# 13_PHY_FE_33-40.net
KiCad netlist of a schematic drawn in Altium Designer
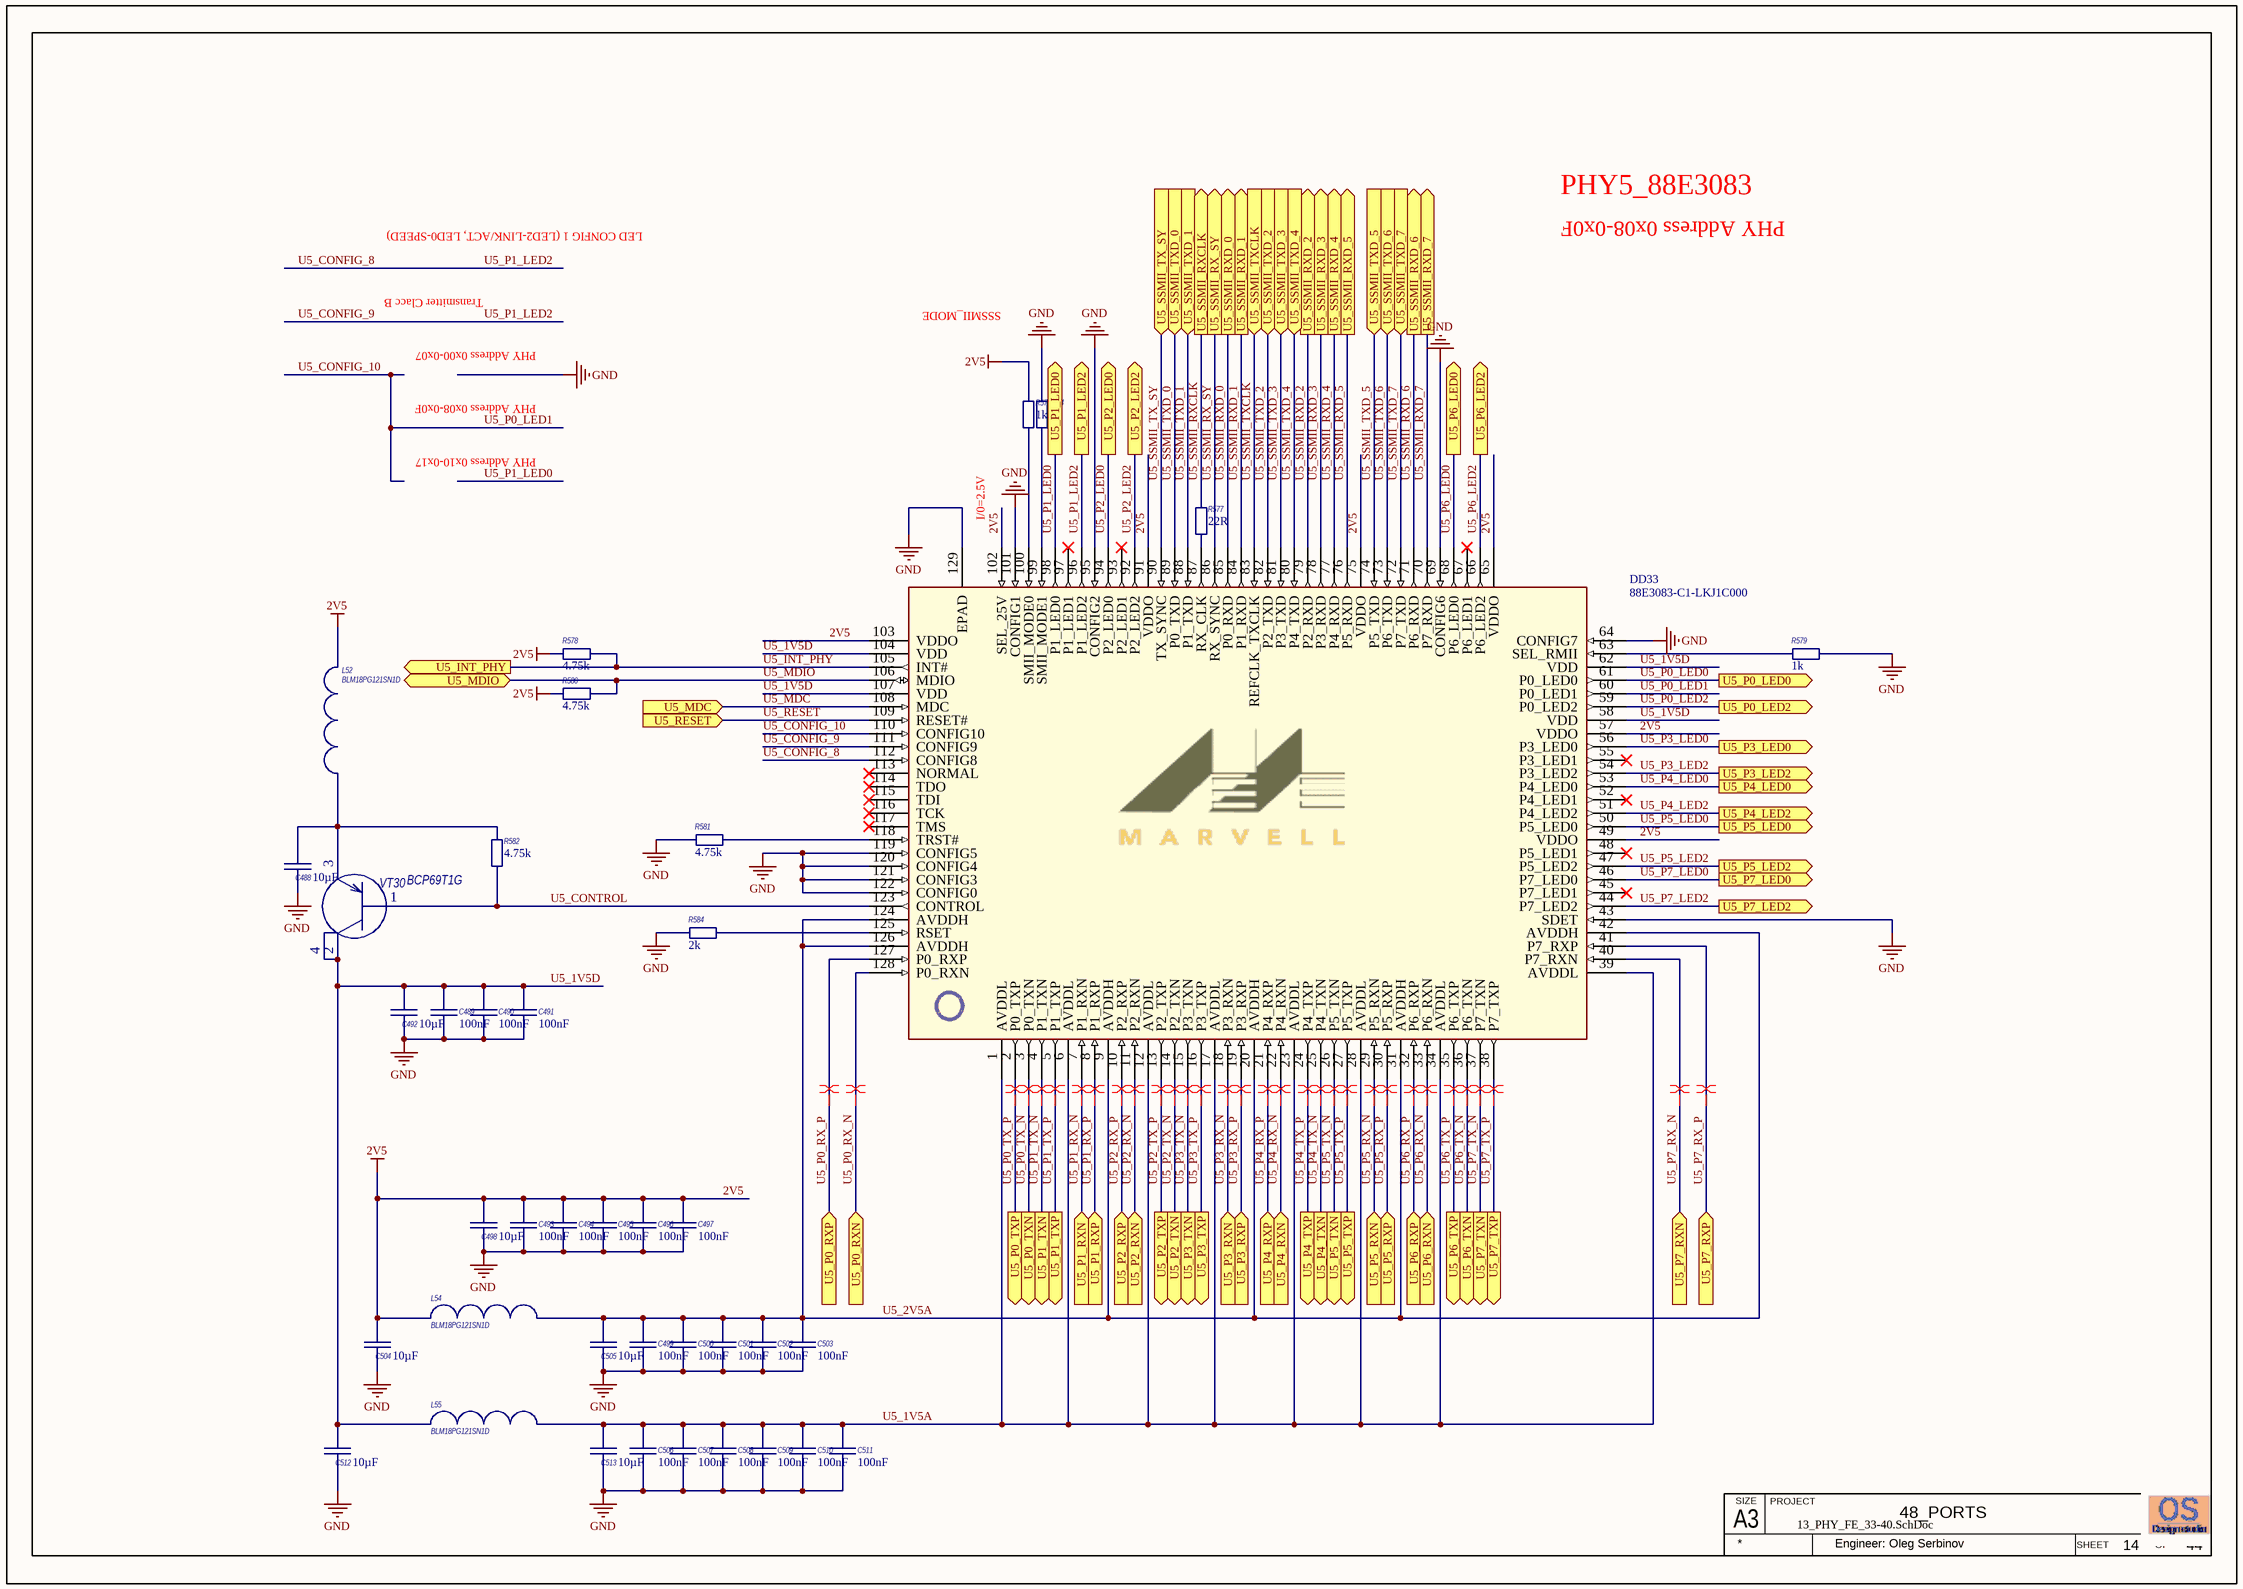
[diagram p0: 13_PHY_FE_33-40.SchDoc]

(export (version "E")
  (design (tool "Eeschema 10.0.6"))
  (components
    (comp (ref "C488")
      (value "GRM21BR61C106KE15")
      (footprint "CAPC2012[0805]")
      (description "C0805, 10uF 10%, 16V, X5R")
      (fields
        (field (name "MANUFACTURER") "Murata")
        (field (name "TOLERANCE") "±10%")
        (field (name "CAPACITANCE") "10µF")
      )
      (libsource (lib "CAPACITORS") (part "GRM21BR61C106KE15"))
    )
    (comp (ref "C489")
      (value "GRM155R71E104KE14D")
      (footprint "C0402_IPC High Density")
      (description "C0402, 100nF, 25V, X7R")
      (fields
        (field (name "MANUFACTURER") "Murata")
        (field (name "CAPACITANCE") "100nF")
        (field (name "CUSTOMER PART NUMBER") "Конденсатор, 100n, 0402, 25V, X7R, 10%")
      )
      (libsource (lib "CAPACITORS") (part "GRM155R71E104KE14D"))
    )
    (comp (ref "C490")
      (value "GRM155R71E104KE14D")
      (footprint "C0402_IPC High Density")
      (description "C0402, 100nF, 25V, X7R")
      (fields
        (field (name "MANUFACTURER") "Murata")
        (field (name "CAPACITANCE") "100nF")
        (field (name "CUSTOMER PART NUMBER") "Конденсатор, 100n, 0402, 25V, X7R, 10%")
      )
      (libsource (lib "CAPACITORS") (part "GRM155R71E104KE14D"))
    )
    (comp (ref "C491")
      (value "GRM155R71E104KE14D")
      (footprint "C0402_IPC High Density")
      (description "C0402, 100nF, 25V, X7R")
      (fields
        (field (name "MANUFACTURER") "Murata")
        (field (name "CAPACITANCE") "100nF")
        (field (name "CUSTOMER PART NUMBER") "Конденсатор, 100n, 0402, 25V, X7R, 10%")
      )
      (libsource (lib "CAPACITORS") (part "GRM155R71E104KE14D"))
    )
    (comp (ref "C492")
      (value "GRM21BR61C106KE15")
      (footprint "CAPC2012[0805]")
      (description "C0805, 10uF 10%, 16V, X5R")
      (fields
        (field (name "MANUFACTURER") "Murata")
        (field (name "TOLERANCE") "±10%")
        (field (name "CAPACITANCE") "10µF")
      )
      (libsource (lib "CAPACITORS") (part "GRM21BR61C106KE15"))
    )
    (comp (ref "C493")
      (value "GRM155R71E104KE14D")
      (footprint "C0402_IPC High Density")
      (description "C0402, 100nF, 25V, X7R")
      (fields
        (field (name "MANUFACTURER") "Murata")
        (field (name "CAPACITANCE") "100nF")
        (field (name "CUSTOMER PART NUMBER") "Конденсатор, 100n, 0402, 25V, X7R, 10%")
      )
      (libsource (lib "CAPACITORS") (part "GRM155R71E104KE14D"))
    )
    (comp (ref "C494")
      (value "GRM155R71E104KE14D")
      (footprint "C0402_IPC High Density")
      (description "C0402, 100nF, 25V, X7R")
      (fields
        (field (name "MANUFACTURER") "Murata")
        (field (name "CAPACITANCE") "100nF")
        (field (name "CUSTOMER PART NUMBER") "Конденсатор, 100n, 0402, 25V, X7R, 10%")
      )
      (libsource (lib "CAPACITORS") (part "GRM155R71E104KE14D"))
    )
    (comp (ref "C495")
      (value "GRM155R71E104KE14D")
      (footprint "C0402_IPC High Density")
      (description "C0402, 100nF, 25V, X7R")
      (fields
        (field (name "MANUFACTURER") "Murata")
        (field (name "CAPACITANCE") "100nF")
        (field (name "CUSTOMER PART NUMBER") "Конденсатор, 100n, 0402, 25V, X7R, 10%")
      )
      (libsource (lib "CAPACITORS") (part "GRM155R71E104KE14D"))
    )
    (comp (ref "C496")
      (value "GRM155R71E104KE14D")
      (footprint "C0402_IPC High Density")
      (description "C0402, 100nF, 25V, X7R")
      (fields
        (field (name "MANUFACTURER") "Murata")
        (field (name "CAPACITANCE") "100nF")
        (field (name "CUSTOMER PART NUMBER") "Конденсатор, 100n, 0402, 25V, X7R, 10%")
      )
      (libsource (lib "CAPACITORS") (part "GRM155R71E104KE14D"))
    )
    (comp (ref "C497")
      (value "GRM155R71E104KE14D")
      (footprint "C0402_IPC High Density")
      (description "C0402, 100nF, 25V, X7R")
      (fields
        (field (name "MANUFACTURER") "Murata")
        (field (name "CAPACITANCE") "100nF")
        (field (name "CUSTOMER PART NUMBER") "Конденсатор, 100n, 0402, 25V, X7R, 10%")
      )
      (libsource (lib "CAPACITORS") (part "GRM155R71E104KE14D"))
    )
    (comp (ref "C498")
      (value "GRM21BR61C106KE15")
      (footprint "CAPC2012[0805]")
      (description "C0805, 10uF 10%, 16V, X5R")
      (fields
        (field (name "MANUFACTURER") "Murata")
        (field (name "TOLERANCE") "±10%")
        (field (name "CAPACITANCE") "10µF")
      )
      (libsource (lib "CAPACITORS") (part "GRM21BR61C106KE15"))
    )
    (comp (ref "C499")
      (value "GRM155R71E104KE14D")
      (footprint "C0402_IPC High Density")
      (description "C0402, 100nF, 25V, X7R")
      (fields
        (field (name "MANUFACTURER") "Murata")
        (field (name "CAPACITANCE") "100nF")
        (field (name "CUSTOMER PART NUMBER") "Конденсатор, 100n, 0402, 25V, X7R, 10%")
      )
      (libsource (lib "CAPACITORS") (part "GRM155R71E104KE14D"))
    )
    (comp (ref "C500")
      (value "GRM155R71E104KE14D")
      (footprint "C0402_IPC High Density")
      (description "C0402, 100nF, 25V, X7R")
      (fields
        (field (name "MANUFACTURER") "Murata")
        (field (name "CAPACITANCE") "100nF")
        (field (name "CUSTOMER PART NUMBER") "Конденсатор, 100n, 0402, 25V, X7R, 10%")
      )
      (libsource (lib "CAPACITORS") (part "GRM155R71E104KE14D"))
    )
    (comp (ref "C501")
      (value "GRM155R71E104KE14D")
      (footprint "C0402_IPC High Density")
      (description "C0402, 100nF, 25V, X7R")
      (fields
        (field (name "MANUFACTURER") "Murata")
        (field (name "CAPACITANCE") "100nF")
        (field (name "CUSTOMER PART NUMBER") "Конденсатор, 100n, 0402, 25V, X7R, 10%")
      )
      (libsource (lib "CAPACITORS") (part "GRM155R71E104KE14D"))
    )
    (comp (ref "C502")
      (value "GRM155R71E104KE14D")
      (footprint "C0402_IPC High Density")
      (description "C0402, 100nF, 25V, X7R")
      (fields
        (field (name "MANUFACTURER") "Murata")
        (field (name "CAPACITANCE") "100nF")
        (field (name "CUSTOMER PART NUMBER") "Конденсатор, 100n, 0402, 25V, X7R, 10%")
      )
      (libsource (lib "CAPACITORS") (part "GRM155R71E104KE14D"))
    )
    (comp (ref "C503")
      (value "GRM155R71E104KE14D")
      (footprint "C0402_IPC High Density")
      (description "C0402, 100nF, 25V, X7R")
      (fields
        (field (name "MANUFACTURER") "Murata")
        (field (name "CAPACITANCE") "100nF")
        (field (name "CUSTOMER PART NUMBER") "Конденсатор, 100n, 0402, 25V, X7R, 10%")
      )
      (libsource (lib "CAPACITORS") (part "GRM155R71E104KE14D"))
    )
    (comp (ref "C504")
      (value "GRM21BR61C106KE15")
      (footprint "CAPC2012[0805]")
      (description "C0805, 10uF 10%, 16V, X5R")
      (fields
        (field (name "MANUFACTURER") "Murata")
        (field (name "TOLERANCE") "±10%")
        (field (name "CAPACITANCE") "10µF")
      )
      (libsource (lib "CAPACITORS") (part "GRM21BR61C106KE15"))
    )
    (comp (ref "C505")
      (value "GRM21BR61C106KE15")
      (footprint "CAPC2012[0805]")
      (description "C0805, 10uF 10%, 16V, X5R")
      (fields
        (field (name "MANUFACTURER") "Murata")
        (field (name "TOLERANCE") "±10%")
        (field (name "CAPACITANCE") "10µF")
      )
      (libsource (lib "CAPACITORS") (part "GRM21BR61C106KE15"))
    )
    (comp (ref "C506")
      (value "GRM155R71E104KE14D")
      (footprint "C0402_IPC High Density")
      (description "C0402, 100nF, 25V, X7R")
      (fields
        (field (name "MANUFACTURER") "Murata")
        (field (name "CAPACITANCE") "100nF")
        (field (name "CUSTOMER PART NUMBER") "Конденсатор, 100n, 0402, 25V, X7R, 10%")
      )
      (libsource (lib "CAPACITORS") (part "GRM155R71E104KE14D"))
    )
    (comp (ref "C507")
      (value "GRM155R71E104KE14D")
      (footprint "C0402_IPC High Density")
      (description "C0402, 100nF, 25V, X7R")
      (fields
        (field (name "MANUFACTURER") "Murata")
        (field (name "CAPACITANCE") "100nF")
        (field (name "CUSTOMER PART NUMBER") "Конденсатор, 100n, 0402, 25V, X7R, 10%")
      )
      (libsource (lib "CAPACITORS") (part "GRM155R71E104KE14D"))
    )
    (comp (ref "C508")
      (value "GRM155R71E104KE14D")
      (footprint "C0402_IPC High Density")
      (description "C0402, 100nF, 25V, X7R")
      (fields
        (field (name "MANUFACTURER") "Murata")
        (field (name "CAPACITANCE") "100nF")
        (field (name "CUSTOMER PART NUMBER") "Конденсатор, 100n, 0402, 25V, X7R, 10%")
      )
      (libsource (lib "CAPACITORS") (part "GRM155R71E104KE14D"))
    )
    (comp (ref "C509")
      (value "GRM155R71E104KE14D")
      (footprint "C0402_IPC High Density")
      (description "C0402, 100nF, 25V, X7R")
      (fields
        (field (name "MANUFACTURER") "Murata")
        (field (name "CAPACITANCE") "100nF")
        (field (name "CUSTOMER PART NUMBER") "Конденсатор, 100n, 0402, 25V, X7R, 10%")
      )
      (libsource (lib "CAPACITORS") (part "GRM155R71E104KE14D"))
    )
    (comp (ref "C510")
      (value "GRM155R71E104KE14D")
      (footprint "C0402_IPC High Density")
      (description "C0402, 100nF, 25V, X7R")
      (fields
        (field (name "MANUFACTURER") "Murata")
        (field (name "CAPACITANCE") "100nF")
        (field (name "CUSTOMER PART NUMBER") "Конденсатор, 100n, 0402, 25V, X7R, 10%")
      )
      (libsource (lib "CAPACITORS") (part "GRM155R71E104KE14D"))
    )
    (comp (ref "C511")
      (value "GRM155R71E104KE14D")
      (footprint "C0402_IPC High Density")
      (description "C0402, 100nF, 25V, X7R")
      (fields
        (field (name "MANUFACTURER") "Murata")
        (field (name "CAPACITANCE") "100nF")
        (field (name "CUSTOMER PART NUMBER") "Конденсатор, 100n, 0402, 25V, X7R, 10%")
      )
      (libsource (lib "CAPACITORS") (part "GRM155R71E104KE14D"))
    )
    (comp (ref "C512")
      (value "GRM21BR61C106KE15")
      (footprint "CAPC2012[0805]")
      (description "C0805, 10uF 10%, 16V, X5R")
      (fields
        (field (name "MANUFACTURER") "Murata")
        (field (name "TOLERANCE") "±10%")
        (field (name "CAPACITANCE") "10µF")
      )
      (libsource (lib "CAPACITORS") (part "GRM21BR61C106KE15"))
    )
    (comp (ref "C513")
      (value "GRM21BR61C106KE15")
      (footprint "CAPC2012[0805]")
      (description "C0805, 10uF 10%, 16V, X5R")
      (fields
        (field (name "MANUFACTURER") "Murata")
        (field (name "TOLERANCE") "±10%")
        (field (name "CAPACITANCE") "10µF")
      )
      (libsource (lib "CAPACITORS") (part "GRM21BR61C106KE15"))
    )
    (comp (ref "DD33")
      (value "88E3083-C1-LKJ1C000")
      (footprint "LQFP-128N")
      (description "IC 10/100BASE-T OCTAL PHY")
      (fields
        (field (name "CUSTOMER PART NUMBER") "Микросхема, 88E3083-C1-LKJ1C000, IC 10/100BASE-T OCTAL PHY, 128 LQFP")
        (field (name "MANUFACTURER") "Marvell Technology Group")
      )
      (libsource (lib "DIGITAL and ANALIG ICs") (part "88E3083-C1-LKJ1C000"))
    )
    (comp (ref "L52")
      (value "BLM18PG121SN1D")
      (footprint "INDC1608X95N")
      (description "FILTER BLM18 (0603, 2A)")
      (fields
        (field (name "MANUFACTURER") "Murata")
        (field (name "RPART NUMBER") "MPZ1608S121ATAH0 ; CIC10P121NC ; MPZ1608S121ATDH5 ; BLM18PG121SH1D ; 742792625")
      )
      (libsource (lib "INDUCTORS") (part "BLM18PG121SN1D"))
    )
    (comp (ref "L54")
      (value "BLM18PG121SN1D")
      (footprint "INDC1608X95N")
      (description "FILTER BLM18 (0603, 2A)")
      (fields
        (field (name "MANUFACTURER") "Murata")
        (field (name "RPART NUMBER") "MPZ1608S121ATAH0 ; CIC10P121NC ; MPZ1608S121ATDH5 ; BLM18PG121SH1D ; 742792625")
      )
      (libsource (lib "INDUCTORS") (part "BLM18PG121SN1D"))
    )
    (comp (ref "L55")
      (value "BLM18PG121SN1D")
      (footprint "INDC1608X95N")
      (description "FILTER BLM18 (0603, 2A)")
      (fields
        (field (name "MANUFACTURER") "Murata")
        (field (name "RPART NUMBER") "MPZ1608S121ATAH0 ; CIC10P121NC ; MPZ1608S121ATDH5 ; BLM18PG121SH1D ; 742792625")
      )
      (libsource (lib "INDUCTORS") (part "BLM18PG121SN1D"))
    )
    (comp (ref "R573")
      (value "ERJ-2RKF1001X")
      (footprint "R0402_IPC High Density")
      (description "R0402, 1k 1%")
      (fields
        (field (name "MANUFACTURER") "Panasonic")
        (field (name "TOLERANCE") "1 %")
        (field (name "RESISTANCE") "1k")
      )
      (libsource (lib "RESISTOR") (part "ERJ-2RKF1001X"))
    )
    (comp (ref "R574")
      (value "ERJ-2RKF1001X")
      (footprint "R0402_IPC High Density")
      (description "R0402, 1k 1%")
      (fields
        (field (name "MANUFACTURER") "Panasonic")
        (field (name "TOLERANCE") "1 %")
        (field (name "RESISTANCE") "1k")
      )
      (libsource (lib "RESISTOR") (part "ERJ-2RKF1001X"))
    )
    (comp (ref "R577")
      (value "ERJ-2RKF22R0X")
      (footprint "R0402_IPC High Density")
      (description "R0402, 22R 1%")
      (fields
        (field (name "MANUFACTURER") "Panasonic")
        (field (name "RESISTANCE") "22R")
        (field (name "CUSTOMER PART NUMBER") "Резистор, 22R, 0402, 1%")
      )
      (libsource (lib "RESISTOR") (part "ERJ-2RKF22R0X"))
    )
    (comp (ref "R578")
      (value "ERJ-2RKF4751X")
      (footprint "R0402_IPC High Density")
      (description "R0402, 4.75k 1%")
      (fields
        (field (name "TOLERANCE") "±1%")
        (field (name "MANUFACTURER") "Panasonic")
        (field (name "RESISTANCE (OHMS)") "4.75k")
      )
      (libsource (lib "RESISTOR") (part "ERJ-2RKF4751X"))
    )
    (comp (ref "R579")
      (value "ERJ-2RKF1001X")
      (footprint "R0402_IPC High Density")
      (description "R0402, 1k 1%")
      (fields
        (field (name "MANUFACTURER") "Panasonic")
        (field (name "TOLERANCE") "1 %")
        (field (name "RESISTANCE") "1k")
      )
      (libsource (lib "RESISTOR") (part "ERJ-2RKF1001X"))
    )
    (comp (ref "R580")
      (value "ERJ-2RKF4751X")
      (footprint "R0402_IPC High Density")
      (description "R0402, 4.75k 1%")
      (fields
        (field (name "TOLERANCE") "±1%")
        (field (name "MANUFACTURER") "Panasonic")
        (field (name "RESISTANCE (OHMS)") "4.75k")
      )
      (libsource (lib "RESISTOR") (part "ERJ-2RKF4751X"))
    )
    (comp (ref "R581")
      (value "ERJ-2RKF4751X")
      (footprint "R0402_IPC High Density")
      (description "R0402, 4.75k 1%")
      (fields
        (field (name "TOLERANCE") "±1%")
        (field (name "MANUFACTURER") "Panasonic")
        (field (name "RESISTANCE (OHMS)") "4.75k")
      )
      (libsource (lib "RESISTOR") (part "ERJ-2RKF4751X"))
    )
    (comp (ref "R582")
      (value "ERJ-2RKF4751X")
      (footprint "R0402_IPC High Density")
      (description "R0402, 4.75k 1%")
      (fields
        (field (name "TOLERANCE") "±1%")
        (field (name "MANUFACTURER") "Panasonic")
        (field (name "RESISTANCE (OHMS)") "4.75k")
      )
      (libsource (lib "RESISTOR") (part "ERJ-2RKF4751X"))
    )
    (comp (ref "R584")
      (value "ERJ-2RKF2001X")
      (footprint "R0402_IPC High Density")
      (description "R0402, 2k 1%")
      (fields
        (field (name "TOLERANCE") "±1%")
        (field (name "MANUFACTURER") "Panasonic")
        (field (name "RESISTANCE (OHMS)") "2k")
      )
      (libsource (lib "RESISTOR") (part "ERJ-2RKF2001X"))
    )
    (comp (ref "VT30")
      (value "BCP69T1G")
      (footprint "SOT223_N")
      (description "TRANSISTOR PNP -20V -1A SOT-223")
      (fields
        (field (name "MANUFACTURER") "ON Semiconductor")
        (field (name "MANUFACTURER PART NUMBER") "BCP69T1")
      )
      (libsource (lib "TRANSISTORS") (part "BCP69T1"))
    )
  )
  (nets
    (net (code "1") (name "/U5_1V5A") (class "Default")
      (node (ref "C506") (pin "2") (pintype "passive"))
      (node (ref "C507") (pin "2") (pintype "passive"))
      (node (ref "C508") (pin "2") (pintype "passive"))
      (node (ref "C509") (pin "2") (pintype "passive"))
      (node (ref "C510") (pin "2") (pintype "passive"))
      (node (ref "C511") (pin "2") (pintype "passive"))
      (node (ref "C513") (pin "2") (pintype "passive"))
      (node (ref "DD33") (pin "1") (pinfunction "AVDDL_1") (pintype "power_in"))
      (node (ref "DD33") (pin "12") (pinfunction "AVDDL_12") (pintype "power_in"))
      (node (ref "DD33") (pin "17") (pinfunction "AVDDL_17") (pintype "power_in"))
      (node (ref "DD33") (pin "23") (pinfunction "AVDDL_23") (pintype "power_in"))
      (node (ref "DD33") (pin "28") (pinfunction "AVDDL_28") (pintype "power_in"))
      (node (ref "DD33") (pin "34") (pinfunction "AVDDL_34") (pintype "power_in"))
      (node (ref "DD33") (pin "39") (pinfunction "AVDDL_39") (pintype "power_in"))
      (node (ref "DD33") (pin "6") (pinfunction "AVDDL_6") (pintype "power_in"))
      (node (ref "L55") (pin "2") (pinfunction "2_2") (pintype "passive"))
    )
    (net (code "2") (name "/U5_1V5D") (class "Default")
      (node (ref "C489") (pin "2") (pintype "passive"))
      (node (ref "C490") (pin "2") (pintype "passive"))
      (node (ref "C491") (pin "2") (pintype "passive"))
      (node (ref "C492") (pin "2") (pintype "passive"))
      (node (ref "C512") (pin "2") (pintype "passive"))
      (node (ref "DD33") (pin "104") (pinfunction "VDD_104") (pintype "power_in"))
      (node (ref "DD33") (pin "107") (pinfunction "VDD_107") (pintype "power_in"))
      (node (ref "DD33") (pin "58") (pinfunction "VDD_58") (pintype "power_in"))
      (node (ref "DD33") (pin "62") (pinfunction "VDD_62") (pintype "power_in"))
      (node (ref "L55") (pin "1") (pinfunction "1_1") (pintype "passive"))
      (node (ref "VT30") (pin "2") (pinfunction "K_2") (pintype "passive"))
      (node (ref "VT30") (pin "4") (pinfunction "K_4") (pintype "passive"))
    )
    (net (code "3") (name "/U5_2V5A") (class "Default")
      (node (ref "C499") (pin "2") (pintype "passive"))
      (node (ref "C500") (pin "2") (pintype "passive"))
      (node (ref "C501") (pin "2") (pintype "passive"))
      (node (ref "C502") (pin "2") (pintype "passive"))
      (node (ref "C503") (pin "2") (pintype "passive"))
      (node (ref "C505") (pin "2") (pintype "passive"))
      (node (ref "DD33") (pin "124") (pinfunction "AVDDH_124") (pintype "power_in"))
      (node (ref "DD33") (pin "126") (pinfunction "AVDDH_126") (pintype "power_in"))
      (node (ref "DD33") (pin "20") (pinfunction "AVDDH_20") (pintype "power_in"))
      (node (ref "DD33") (pin "31") (pinfunction "AVDDH_31") (pintype "power_in"))
      (node (ref "DD33") (pin "42") (pinfunction "AVDDH_42") (pintype "power_in"))
      (node (ref "DD33") (pin "9") (pinfunction "AVDDH_9") (pintype "power_in"))
      (node (ref "L54") (pin "2") (pinfunction "2_2") (pintype "passive"))
    )
    (net (code "4") (name "/U5_CONFIG_8") (class "Default")
      (node (ref "DD33") (pin "111") (pinfunction "CONFIG9_111") (pintype "input"))
      (node (ref "DD33") (pin "112") (pinfunction "CONFIG8_112") (pintype "input"))
      (node (ref "DD33") (pin "96") (pinfunction "P1_LED2_96") (pintype "output"))
    )
    (net (code "5") (name "/U5_CONFIG_10") (class "Default")
      (node (ref "DD33") (pin "110") (pinfunction "CONFIG10_110") (pintype "input"))
      (node (ref "DD33") (pin "60") (pinfunction "P0_LED1_60") (pintype "output"))
    )
    (net (code "6") (name "/U5_CONTROL") (class "Default")
      (node (ref "DD33") (pin "123") (pinfunction "CONTROL_123") (pintype "output"))
      (node (ref "R582") (pin "1") (pintype "passive"))
      (node (ref "VT30") (pin "1") (pinfunction "B_1") (pintype "passive"))
    )
    (net (code "7") (name "/U5_INT_PHY") (class "Default")
      (node (ref "DD33") (pin "105") (pinfunction "INT#_105") (pintype "output"))
      (node (ref "R578") (pin "2") (pintype "passive"))
    )
    (net (code "8") (name "/U5_MDC") (class "Default")
      (node (ref "DD33") (pin "108") (pinfunction "MDC_108") (pintype "input"))
    )
    (net (code "9") (name "/U5_MDIO") (class "Default")
      (node (ref "DD33") (pin "106") (pinfunction "MDIO_106") (pintype "bidirectional"))
      (node (ref "R580") (pin "2") (pintype "passive"))
    )
    (net (code "10") (name "/U5_P0_LED0") (class "Default")
      (node (ref "DD33") (pin "61") (pinfunction "P0_LED0_61") (pintype "output"))
    )
    (net (code "11") (name "/U5_P0_LED2") (class "Default")
      (node (ref "DD33") (pin "59") (pinfunction "P0_LED2_59") (pintype "output"))
    )
    (net (code "12") (name "/U5_P0_RX_N") (class "Default")
      (node (ref "DD33") (pin "128") (pinfunction "P0_RXN_128") (pintype "input"))
    )
    (net (code "13") (name "/U5_P0_RX_P") (class "Default")
      (node (ref "DD33") (pin "127") (pinfunction "P0_RXP_127") (pintype "input"))
    )
    (net (code "14") (name "/U5_P0_TX_N") (class "Default")
      (node (ref "DD33") (pin "3") (pinfunction "P0_TXN_3") (pintype "output"))
    )
    (net (code "15") (name "/U5_P0_TX_P") (class "Default")
      (node (ref "DD33") (pin "2") (pinfunction "P0_TXP_2") (pintype "output"))
    )
    (net (code "16") (name "/U5_P1_LED0") (class "Default")
      (node (ref "DD33") (pin "98") (pinfunction "P1_LED0_98") (pintype "output"))
    )
    (net (code "17") (name "/U5_P1_RX_N") (class "Default")
      (node (ref "DD33") (pin "7") (pinfunction "P1_RXN_7") (pintype "input"))
    )
    (net (code "18") (name "/U5_P1_RX_P") (class "Default")
      (node (ref "DD33") (pin "8") (pinfunction "P1_RXP_8") (pintype "input"))
    )
    (net (code "19") (name "/U5_P1_TX_N") (class "Default")
      (node (ref "DD33") (pin "4") (pinfunction "P1_TXN_4") (pintype "output"))
    )
    (net (code "20") (name "/U5_P1_TX_P") (class "Default")
      (node (ref "DD33") (pin "5") (pinfunction "P1_TXP_5") (pintype "output"))
    )
    (net (code "21") (name "/U5_P2_LED0") (class "Default")
      (node (ref "DD33") (pin "94") (pinfunction "P2_LED0_94") (pintype "output"))
    )
    (net (code "22") (name "/U5_P2_LED2") (class "Default")
      (node (ref "DD33") (pin "92") (pinfunction "P2_LED2_92") (pintype "output"))
    )
    (net (code "23") (name "/U5_P2_RX_N") (class "Default")
      (node (ref "DD33") (pin "11") (pinfunction "P2_RXN_11") (pintype "input"))
    )
    (net (code "24") (name "/U5_P2_RX_P") (class "Default")
      (node (ref "DD33") (pin "10") (pinfunction "P2_RXP_10") (pintype "input"))
    )
    (net (code "25") (name "/U5_P2_TX_N") (class "Default")
      (node (ref "DD33") (pin "14") (pinfunction "P2_TXN_14") (pintype "output"))
    )
    (net (code "26") (name "/U5_P2_TX_P") (class "Default")
      (node (ref "DD33") (pin "13") (pinfunction "P2_TXP_13") (pintype "output"))
    )
    (net (code "27") (name "/U5_P3_LED0") (class "Default")
      (node (ref "DD33") (pin "56") (pinfunction "P3_LED0_56") (pintype "output"))
    )
    (net (code "28") (name "/U5_P3_LED2") (class "Default")
      (node (ref "DD33") (pin "54") (pinfunction "P3_LED2_54") (pintype "output"))
    )
    (net (code "29") (name "/U5_P3_RX_N") (class "Default")
      (node (ref "DD33") (pin "18") (pinfunction "P3_RXN_18") (pintype "input"))
    )
    (net (code "30") (name "/U5_P3_RX_P") (class "Default")
      (node (ref "DD33") (pin "19") (pinfunction "P3_RXP_19") (pintype "input"))
    )
    (net (code "31") (name "/U5_P3_TX_N") (class "Default")
      (node (ref "DD33") (pin "15") (pinfunction "P3_TXN_15") (pintype "output"))
    )
    (net (code "32") (name "/U5_P3_TX_P") (class "Default")
      (node (ref "DD33") (pin "16") (pinfunction "P3_TXP_16") (pintype "output"))
    )
    (net (code "33") (name "/U5_P4_LED0") (class "Default")
      (node (ref "DD33") (pin "53") (pinfunction "P4_LED0_53") (pintype "output"))
    )
    (net (code "34") (name "/U5_P4_LED2") (class "Default")
      (node (ref "DD33") (pin "51") (pinfunction "P4_LED2_51") (pintype "output"))
    )
    (net (code "35") (name "/U5_P4_RX_N") (class "Default")
      (node (ref "DD33") (pin "22") (pinfunction "P4_RXN_22") (pintype "input"))
    )
    (net (code "36") (name "/U5_P4_RX_P") (class "Default")
      (node (ref "DD33") (pin "21") (pinfunction "P4_RXP_21") (pintype "input"))
    )
    (net (code "37") (name "/U5_P4_TX_N") (class "Default")
      (node (ref "DD33") (pin "25") (pinfunction "P4_TXN_25") (pintype "output"))
    )
    (net (code "38") (name "/U5_P4_TX_P") (class "Default")
      (node (ref "DD33") (pin "24") (pinfunction "P4_TXP_24") (pintype "output"))
    )
    (net (code "39") (name "/U5_P5_LED0") (class "Default")
      (node (ref "DD33") (pin "50") (pinfunction "P5_LED0_50") (pintype "output"))
    )
    (net (code "40") (name "/U5_P5_LED2") (class "Default")
      (node (ref "DD33") (pin "47") (pinfunction "P5_LED2_47") (pintype "output"))
    )
    (net (code "41") (name "/U5_P5_RX_N") (class "Default")
      (node (ref "DD33") (pin "29") (pinfunction "P5_RXN_29") (pintype "input"))
    )
    (net (code "42") (name "/U5_P5_RX_P") (class "Default")
      (node (ref "DD33") (pin "30") (pinfunction "P5_RXP_30") (pintype "input"))
    )
    (net (code "43") (name "/U5_P5_TX_N") (class "Default")
      (node (ref "DD33") (pin "26") (pinfunction "P5_TXN_26") (pintype "output"))
    )
    (net (code "44") (name "/U5_P5_TX_P") (class "Default")
      (node (ref "DD33") (pin "27") (pinfunction "P5_TXP_27") (pintype "output"))
    )
    (net (code "45") (name "/U5_P6_LED0") (class "Default")
      (node (ref "DD33") (pin "68") (pinfunction "P6_LED0_68") (pintype "output"))
    )
    (net (code "46") (name "/U5_P6_LED2") (class "Default")
      (node (ref "DD33") (pin "66") (pinfunction "P6_LED2_66") (pintype "output"))
    )
    (net (code "47") (name "/U5_P6_RX_N") (class "Default")
      (node (ref "DD33") (pin "33") (pinfunction "P6_RXN_33") (pintype "input"))
    )
    (net (code "48") (name "/U5_P6_RX_P") (class "Default")
      (node (ref "DD33") (pin "32") (pinfunction "P6_RXP_32") (pintype "input"))
    )
    (net (code "49") (name "/U5_P6_TX_N") (class "Default")
      (node (ref "DD33") (pin "36") (pinfunction "P6_TXN_36") (pintype "output"))
    )
    (net (code "50") (name "/U5_P6_TX_P") (class "Default")
      (node (ref "DD33") (pin "35") (pinfunction "P6_TXP_35") (pintype "output"))
    )
    (net (code "51") (name "/U5_P7_LED0") (class "Default")
      (node (ref "DD33") (pin "46") (pinfunction "P7_LED0_46") (pintype "output"))
    )
    (net (code "52") (name "/U5_P7_LED2") (class "Default")
      (node (ref "DD33") (pin "44") (pinfunction "P7_LED2_44") (pintype "output"))
    )
    (net (code "53") (name "/U5_P7_RX_N") (class "Default")
      (node (ref "DD33") (pin "40") (pinfunction "P7_RXN_40") (pintype "input"))
    )
    (net (code "54") (name "/U5_P7_RX_P") (class "Default")
      (node (ref "DD33") (pin "41") (pinfunction "P7_RXP_41") (pintype "input"))
    )
    (net (code "55") (name "/U5_P7_TX_N") (class "Default")
      (node (ref "DD33") (pin "37") (pinfunction "P7_TXN_37") (pintype "output"))
    )
    (net (code "56") (name "/U5_P7_TX_P") (class "Default")
      (node (ref "DD33") (pin "38") (pinfunction "P7_TXP_38") (pintype "output"))
    )
    (net (code "57") (name "/U5_RESET") (class "Default")
      (node (ref "DD33") (pin "109") (pinfunction "RESET#_109") (pintype "input"))
    )
    (net (code "58") (name "/U5_SSMII_RXCLK") (class "Default")
      (node (ref "R577") (pin "2") (pintype "passive"))
    )
    (net (code "59") (name "/U5_SSMII_RXD_0") (class "Default")
      (node (ref "DD33") (pin "85") (pinfunction "P0_RXD_85") (pintype "output"))
    )
    (net (code "60") (name "/U5_SSMII_RXD_1") (class "Default")
      (node (ref "DD33") (pin "84") (pinfunction "P1_RXD_84") (pintype "output"))
    )
    (net (code "61") (name "/U5_SSMII_RXD_2") (class "Default")
      (node (ref "DD33") (pin "79") (pinfunction "P2_RXD_79") (pintype "output"))
    )
    (net (code "62") (name "/U5_SSMII_RXD_3") (class "Default")
      (node (ref "DD33") (pin "78") (pinfunction "P3_RXD_78") (pintype "output"))
    )
    (net (code "63") (name "/U5_SSMII_RXD_4") (class "Default")
      (node (ref "DD33") (pin "77") (pinfunction "P4_RXD_77") (pintype "output"))
    )
    (net (code "64") (name "/U5_SSMII_RXD_5") (class "Default")
      (node (ref "DD33") (pin "76") (pinfunction "P5_RXD_76") (pintype "output"))
    )
    (net (code "65") (name "/U5_SSMII_RXD_6") (class "Default")
      (node (ref "DD33") (pin "71") (pinfunction "P6_RXD_71") (pintype "output"))
    )
    (net (code "66") (name "/U5_SSMII_RXD_7") (class "Default")
      (node (ref "DD33") (pin "70") (pinfunction "P7_RXD_70") (pintype "output"))
    )
    (net (code "67") (name "/U5_SSMII_RX_SY") (class "Default")
      (node (ref "DD33") (pin "86") (pinfunction "RX_SYNC_86") (pintype "output"))
    )
    (net (code "68") (name "/U5_SSMII_TXCLK") (class "Default")
      (node (ref "DD33") (pin "83") (pinfunction "REFCLK_TXCLK_83") (pintype "input"))
    )
    (net (code "69") (name "/U5_SSMII_TXD_0") (class "Default")
      (node (ref "DD33") (pin "89") (pinfunction "P0_TXD_89") (pintype "input"))
    )
    (net (code "70") (name "/U5_SSMII_TXD_1") (class "Default")
      (node (ref "DD33") (pin "88") (pinfunction "P1_TXD_88") (pintype "input"))
    )
    (net (code "71") (name "/U5_SSMII_TXD_2") (class "Default")
      (node (ref "DD33") (pin "82") (pinfunction "P2_TXD_82") (pintype "input"))
    )
    (net (code "72") (name "/U5_SSMII_TXD_3") (class "Default")
      (node (ref "DD33") (pin "81") (pinfunction "P3_TXD_81") (pintype "input"))
    )
    (net (code "73") (name "/U5_SSMII_TXD_4") (class "Default")
      (node (ref "DD33") (pin "80") (pinfunction "P4_TXD_80") (pintype "input"))
    )
    (net (code "74") (name "/U5_SSMII_TXD_5") (class "Default")
      (node (ref "DD33") (pin "74") (pinfunction "P5_TXD_74") (pintype "input"))
    )
    (net (code "75") (name "/U5_SSMII_TXD_6") (class "Default")
      (node (ref "DD33") (pin "73") (pinfunction "P6_TXD_73") (pintype "input"))
    )
    (net (code "76") (name "/U5_SSMII_TXD_7") (class "Default")
      (node (ref "DD33") (pin "72") (pinfunction "P7_TXD_72") (pintype "input"))
    )
    (net (code "77") (name "/U5_SSMII_TX_SY") (class "Default")
      (node (ref "DD33") (pin "90") (pinfunction "TX_SYNC_90") (pintype "input"))
    )
    (net (code "78") (name "2V5") (class "Default")
      (node (ref "C493") (pin "2") (pintype "passive"))
      (node (ref "C494") (pin "2") (pintype "passive"))
      (node (ref "C495") (pin "2") (pintype "passive"))
      (node (ref "C496") (pin "2") (pintype "passive"))
      (node (ref "C497") (pin "2") (pintype "passive"))
      (node (ref "C498") (pin "2") (pintype "passive"))
      (node (ref "C504") (pin "2") (pintype "passive"))
      (node (ref "DD33") (pin "102") (pinfunction "SEL_25V_102") (pintype "input"))
      (node (ref "DD33") (pin "103") (pinfunction "VDDO_103") (pintype "power_in"))
      (node (ref "DD33") (pin "49") (pinfunction "VDDO_49") (pintype "power_in"))
      (node (ref "DD33") (pin "57") (pinfunction "VDDO_57") (pintype "power_in"))
      (node (ref "DD33") (pin "65") (pinfunction "VDDO_65") (pintype "power_in"))
      (node (ref "DD33") (pin "75") (pinfunction "VDDO_75") (pintype "power_in"))
      (node (ref "DD33") (pin "91") (pinfunction "VDDO_91") (pintype "power_in"))
      (node (ref "L52") (pin "2") (pinfunction "2_2") (pintype "passive"))
      (node (ref "L54") (pin "1") (pinfunction "1_1") (pintype "passive"))
      (node (ref "R573") (pin "2") (pintype "passive"))
      (node (ref "R578") (pin "1") (pintype "passive"))
      (node (ref "R580") (pin "1") (pintype "passive"))
    )
    (net (code "79") (name "GND") (class "Default")
      (node (ref "C488") (pin "1") (pintype "passive"))
      (node (ref "C489") (pin "1") (pintype "passive"))
      (node (ref "C490") (pin "1") (pintype "passive"))
      (node (ref "C491") (pin "1") (pintype "passive"))
      (node (ref "C492") (pin "1") (pintype "passive"))
      (node (ref "C493") (pin "1") (pintype "passive"))
      (node (ref "C494") (pin "1") (pintype "passive"))
      (node (ref "C495") (pin "1") (pintype "passive"))
      (node (ref "C496") (pin "1") (pintype "passive"))
      (node (ref "C497") (pin "1") (pintype "passive"))
      (node (ref "C498") (pin "1") (pintype "passive"))
      (node (ref "C499") (pin "1") (pintype "passive"))
      (node (ref "C500") (pin "1") (pintype "passive"))
      (node (ref "C501") (pin "1") (pintype "passive"))
      (node (ref "C502") (pin "1") (pintype "passive"))
      (node (ref "C503") (pin "1") (pintype "passive"))
      (node (ref "C504") (pin "1") (pintype "passive"))
      (node (ref "C505") (pin "1") (pintype "passive"))
      (node (ref "C506") (pin "1") (pintype "passive"))
      (node (ref "C507") (pin "1") (pintype "passive"))
      (node (ref "C508") (pin "1") (pintype "passive"))
      (node (ref "C509") (pin "1") (pintype "passive"))
      (node (ref "C510") (pin "1") (pintype "passive"))
      (node (ref "C511") (pin "1") (pintype "passive"))
      (node (ref "C512") (pin "1") (pintype "passive"))
      (node (ref "C513") (pin "1") (pintype "passive"))
      (node (ref "DD33") (pin "101") (pinfunction "CONFIG1_101") (pintype "input"))
      (node (ref "DD33") (pin "119") (pinfunction "CONFIG5_119") (pintype "input"))
      (node (ref "DD33") (pin "120") (pinfunction "CONFIG4_120") (pintype "input"))
      (node (ref "DD33") (pin "121") (pinfunction "CONFIG3_121") (pintype "input"))
      (node (ref "DD33") (pin "122") (pinfunction "CONFIG0_122") (pintype "input"))
      (node (ref "DD33") (pin "129") (pinfunction "EPAD_129") (pintype "power_in"))
      (node (ref "DD33") (pin "43") (pinfunction "SDET_43") (pintype "input"))
      (node (ref "DD33") (pin "64") (pinfunction "CONFIG7_64") (pintype "input"))
      (node (ref "DD33") (pin "69") (pinfunction "CONFIG6_69") (pintype "input"))
      (node (ref "DD33") (pin "95") (pinfunction "CONFIG2_95") (pintype "input"))
      (node (ref "R574") (pin "2") (pintype "passive"))
      (node (ref "R579") (pin "1") (pintype "passive"))
      (node (ref "R581") (pin "1") (pintype "passive"))
      (node (ref "R584") (pin "1") (pintype "passive"))
    )
    (net (code "80") (name "Net-(DD33-RSET)") (class "Default")
      (node (ref "DD33") (pin "125") (pinfunction "RSET_125") (pintype "input"))
      (node (ref "R584") (pin "2") (pintype "passive"))
    )
    (net (code "81") (name "Net-(DD33-RX_CLK)") (class "Default")
      (node (ref "DD33") (pin "87") (pinfunction "RX_CLK_87") (pintype "output"))
      (node (ref "R577") (pin "1") (pintype "passive"))
    )
    (net (code "82") (name "Net-(DD33-SEL_RMII)") (class "Default")
      (node (ref "DD33") (pin "63") (pinfunction "SEL_RMII_63") (pintype "input"))
      (node (ref "R579") (pin "2") (pintype "passive"))
    )
    (net (code "83") (name "Net-(DD33-SMII_MODE0)") (class "Default")
      (node (ref "DD33") (pin "100") (pinfunction "SMII_MODE0_100") (pintype "input"))
      (node (ref "R573") (pin "1") (pintype "passive"))
    )
    (net (code "84") (name "Net-(DD33-SMII_MODE1)") (class "Default")
      (node (ref "DD33") (pin "99") (pinfunction "SMII_MODE1_99") (pintype "input"))
      (node (ref "R574") (pin "1") (pintype "passive"))
    )
    (net (code "85") (name "Net-(DD33-TRST#)") (class "Default")
      (node (ref "DD33") (pin "118") (pinfunction "TRST#_118") (pintype "input"))
      (node (ref "R581") (pin "2") (pintype "passive"))
    )
    (net (code "86") (name "Net-(VT30-E)") (class "Default")
      (node (ref "C488") (pin "2") (pintype "passive"))
      (node (ref "L52") (pin "1") (pinfunction "1_1") (pintype "passive"))
      (node (ref "R582") (pin "2") (pintype "passive"))
      (node (ref "VT30") (pin "3") (pinfunction "E_3") (pintype "passive"))
    )
    (net (code "87") (name "unconnected-(DD33-NORMAL-Pad113)") (class "Default")
      (node (ref "DD33") (pin "113") (pinfunction "NORMAL_113") (pintype "passive+no_connect"))
    )
    (net (code "88") (name "unconnected-(DD33-P1_LED1-Pad97)") (class "Default")
      (node (ref "DD33") (pin "97") (pinfunction "P1_LED1_97") (pintype "output+no_connect"))
    )
    (net (code "89") (name "unconnected-(DD33-P2_LED1-Pad93)") (class "Default")
      (node (ref "DD33") (pin "93") (pinfunction "P2_LED1_93") (pintype "output+no_connect"))
    )
    (net (code "90") (name "unconnected-(DD33-P3_LED1-Pad55)") (class "Default")
      (node (ref "DD33") (pin "55") (pinfunction "P3_LED1_55") (pintype "output+no_connect"))
    )
    (net (code "91") (name "unconnected-(DD33-P4_LED1-Pad52)") (class "Default")
      (node (ref "DD33") (pin "52") (pinfunction "P4_LED1_52") (pintype "output+no_connect"))
    )
    (net (code "92") (name "unconnected-(DD33-P5_LED1-Pad48)") (class "Default")
      (node (ref "DD33") (pin "48") (pinfunction "P5_LED1_48") (pintype "output+no_connect"))
    )
    (net (code "93") (name "unconnected-(DD33-P6_LED1-Pad67)") (class "Default")
      (node (ref "DD33") (pin "67") (pinfunction "P6_LED1_67") (pintype "output+no_connect"))
    )
    (net (code "94") (name "unconnected-(DD33-P7_LED1-Pad45)") (class "Default")
      (node (ref "DD33") (pin "45") (pinfunction "P7_LED1_45") (pintype "output+no_connect"))
    )
    (net (code "95") (name "unconnected-(DD33-TCK-Pad116)") (class "Default")
      (node (ref "DD33") (pin "116") (pinfunction "TCK_116") (pintype "passive+no_connect"))
    )
    (net (code "96") (name "unconnected-(DD33-TDI-Pad115)") (class "Default")
      (node (ref "DD33") (pin "115") (pinfunction "TDI_115") (pintype "passive+no_connect"))
    )
    (net (code "97") (name "unconnected-(DD33-TDO-Pad114)") (class "Default")
      (node (ref "DD33") (pin "114") (pinfunction "TDO_114") (pintype "passive+no_connect"))
    )
    (net (code "98") (name "unconnected-(DD33-TMS-Pad117)") (class "Default")
      (node (ref "DD33") (pin "117") (pinfunction "TMS_117") (pintype "passive+no_connect"))
    )
  )
)
